# 3Wheel_MotorDrivers_Encoders.net
KiCad netlist of a schematic drawn in Altium Designer
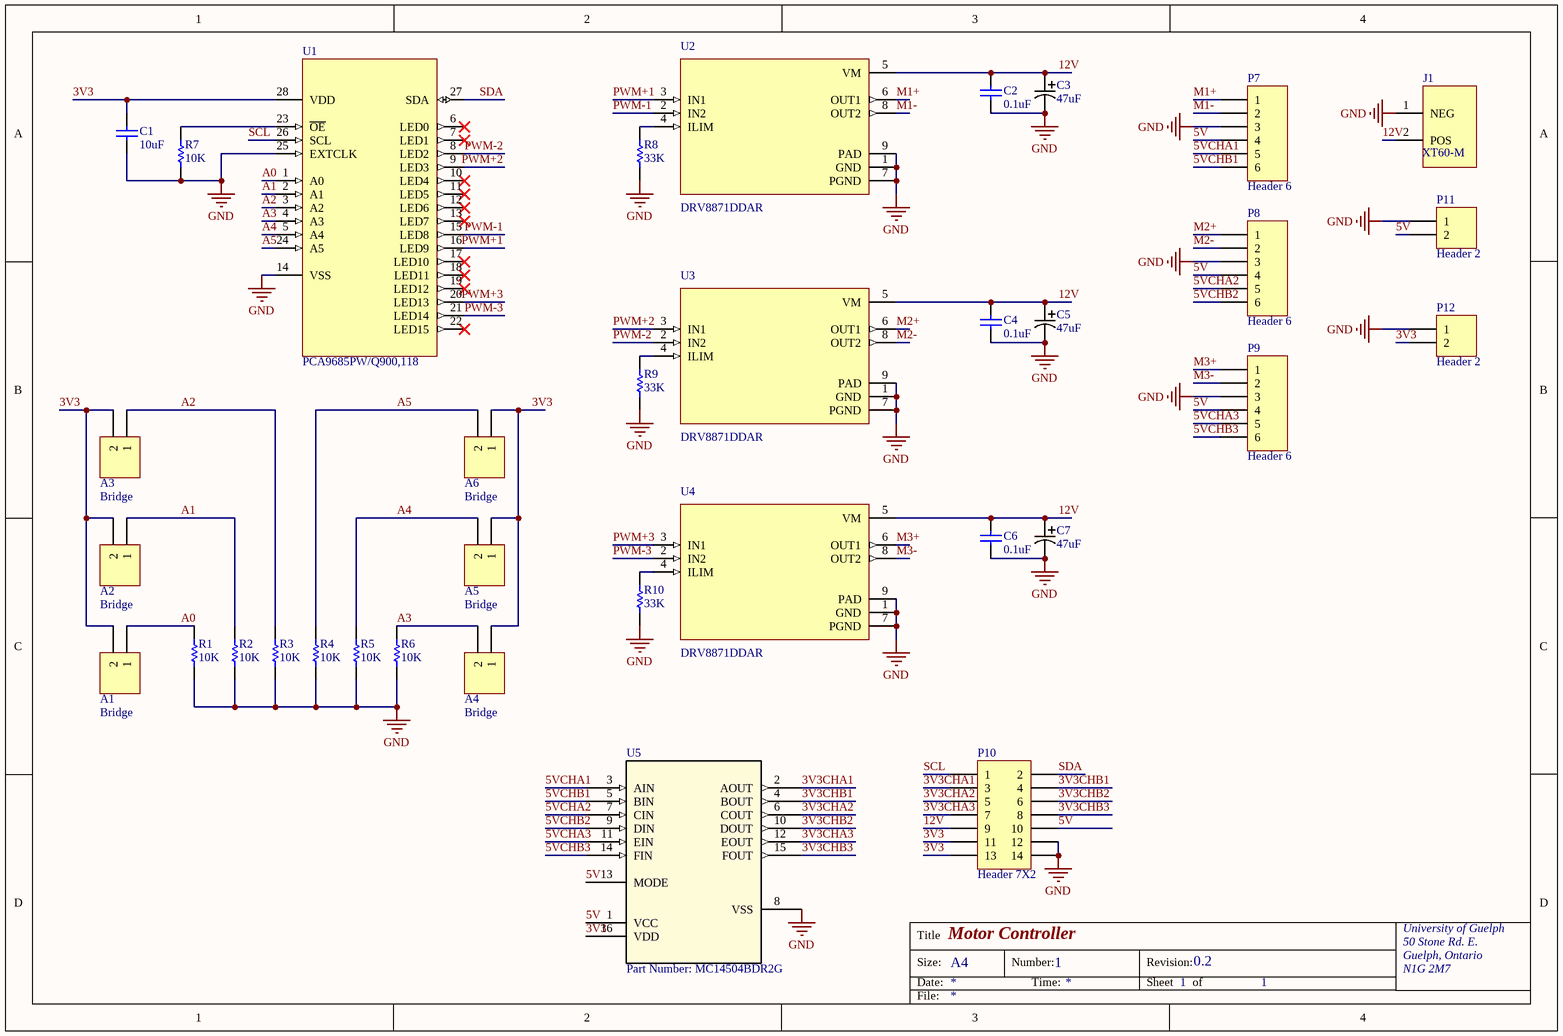
[diagram p0: 3Wheel_MotorDrivers_Encoders.SchDoc]

(export (version "E")
  (design (tool "Eeschema 10.0.6"))
  (components
    (comp (ref "A1")
      (value "Bridge")
      (footprint "0603")
      (description "Header, 2-Pin")
      (fields (field (name "PUBLISHER") "Altium Limited"))
      (libsource (lib "Miscellaneous Connectors") (part "Header 2"))
    )
    (comp (ref "A2")
      (value "Bridge")
      (footprint "0603")
      (description "Header, 2-Pin")
      (fields (field (name "PUBLISHER") "Altium Limited"))
      (libsource (lib "Miscellaneous Connectors") (part "Header 2"))
    )
    (comp (ref "A3")
      (value "Bridge")
      (footprint "0603")
      (description "Header, 2-Pin")
      (fields (field (name "PUBLISHER") "Altium Limited"))
      (libsource (lib "Miscellaneous Connectors") (part "Header 2"))
    )
    (comp (ref "A4")
      (value "Bridge")
      (footprint "0603")
      (description "Header, 2-Pin")
      (fields (field (name "PUBLISHER") "Altium Limited"))
      (libsource (lib "Miscellaneous Connectors") (part "Header 2"))
    )
    (comp (ref "A5")
      (value "Bridge")
      (footprint "0603")
      (description "Header, 2-Pin")
      (fields (field (name "PUBLISHER") "Altium Limited"))
      (libsource (lib "Miscellaneous Connectors") (part "Header 2"))
    )
    (comp (ref "A6")
      (value "Bridge")
      (footprint "0603")
      (description "Header, 2-Pin")
      (fields (field (name "PUBLISHER") "Altium Limited"))
      (libsource (lib "Miscellaneous Connectors") (part "Header 2"))
    )
    (comp (ref "C1")
      (value "10uF")
      (footprint "6-0805_N")
      (description "Capacitor")
      (fields (field (name "Comment") "Cap") (field (name "PUBLISHER") "Altium Limited"))
      (libsource (lib "Miscellaneous Devices") (part "Cap"))
    )
    (comp (ref "C2")
      (value "0.1uF")
      (footprint "6-0805_N")
      (description "Capacitor")
      (fields (field (name "PUBLISHER") "Altium Limited"))
      (libsource (lib "Miscellaneous Devices") (part "Cap"))
    )
    (comp (ref "C3")
      (value "47uF")
      (footprint "PCAP_6.3x7.7-ELE")
      (description "No Description Available")
      (fields
        (field (name "MANUFACTURER_PART_NUMBER") "UWT1H470MCL1GS")
        (field (name "COPYRIGHT") "Copyright (C) 2018 Accelerated Designs. All rights reserved")
      )
      (libsource (lib "2020-02-13_23-38-10") (part "UWT1H470MCL1GS"))
    )
    (comp (ref "C4")
      (value "0.1uF")
      (footprint "6-0805_N")
      (description "Capacitor")
      (fields (field (name "PUBLISHER") "Altium Limited"))
      (libsource (lib "Miscellaneous Devices") (part "Cap"))
    )
    (comp (ref "C5")
      (value "47uF")
      (footprint "PCAP_6.3x7.7-ELE")
      (description "No Description Available")
      (fields
        (field (name "MANUFACTURER_PART_NUMBER") "UWT1H470MCL1GS")
        (field (name "COPYRIGHT") "Copyright (C) 2018 Accelerated Designs. All rights reserved")
      )
      (libsource (lib "2020-02-13_23-38-10") (part "UWT1H470MCL1GS"))
    )
    (comp (ref "C6")
      (value "0.1uF")
      (footprint "6-0805_N")
      (description "Capacitor")
      (fields (field (name "PUBLISHER") "Altium Limited"))
      (libsource (lib "Miscellaneous Devices") (part "Cap"))
    )
    (comp (ref "C7")
      (value "47uF")
      (footprint "PCAP_6.3x7.7-ELE")
      (description "No Description Available")
      (fields
        (field (name "MANUFACTURER_PART_NUMBER") "UWT1H470MCL1GS")
        (field (name "COPYRIGHT") "Copyright (C) 2018 Accelerated Designs. All rights reserved")
      )
      (libsource (lib "2020-02-13_23-38-10") (part "UWT1H470MCL1GS"))
    )
    (comp (ref "J1")
      (value "XT60-M")
      (footprint "*AMASS_XT60-M")
      (description "Plug; DC supply; XT60; male; PIN: 2; for cable; soldered; 30A; 500V")
      (fields (field (name "MF") "AMASS"))
      (libsource (lib "XT60-M") (part "XT60-M"))
    )
    (comp (ref "P7")
      (value "Header 6")
      (footprint "HDR1X6")
      (description "Header, 6-Pin")
      (fields (field (name "PUBLISHER") "Altium Limited"))
      (libsource (lib "Miscellaneous Connectors") (part "Header 6"))
    )
    (comp (ref "P8")
      (value "Header 6")
      (footprint "HDR1X6")
      (description "Header, 6-Pin")
      (fields (field (name "PUBLISHER") "Altium Limited"))
      (libsource (lib "Miscellaneous Connectors") (part "Header 6"))
    )
    (comp (ref "P9")
      (value "Header 6")
      (footprint "HDR1X6")
      (description "Header, 6-Pin")
      (fields (field (name "PUBLISHER") "Altium Limited"))
      (libsource (lib "Miscellaneous Connectors") (part "Header 6"))
    )
    (comp (ref "P10")
      (value "Header 7X2")
      (footprint "HDR2X7")
      (description "Header, 7-Pin, Dual row")
      (fields (field (name "PUBLISHER") "Altium Limited"))
      (libsource (lib "Miscellaneous Connectors") (part "Header 7X2"))
    )
    (comp (ref "P11")
      (value "Header 2")
      (footprint "HDR1X2")
      (description "Header, 2-Pin")
      (fields (field (name "PUBLISHER") "Altium Limited"))
      (libsource (lib "") (part "Header 2_1"))
    )
    (comp (ref "P12")
      (value "Header 2")
      (footprint "HDR1X2")
      (description "Header, 2-Pin")
      (fields (field (name "PUBLISHER") "Altium Limited"))
      (libsource (lib "") (part "Header 2_1"))
    )
    (comp (ref "R1")
      (value "10K")
      (footprint "6-0805_N")
      (description "Resistor")
      (fields (field (name "PUBLISHER") "Altium Limited"))
      (libsource (lib "Miscellaneous Devices") (part "Res1"))
    )
    (comp (ref "R2")
      (value "10K")
      (footprint "6-0805_N")
      (description "Resistor")
      (fields (field (name "PUBLISHER") "Altium Limited"))
      (libsource (lib "Miscellaneous Devices") (part "Res1"))
    )
    (comp (ref "R3")
      (value "10K")
      (footprint "6-0805_N")
      (description "Resistor")
      (fields (field (name "PUBLISHER") "Altium Limited"))
      (libsource (lib "Miscellaneous Devices") (part "Res1"))
    )
    (comp (ref "R4")
      (value "10K")
      (footprint "6-0805_N")
      (description "Resistor")
      (fields (field (name "PUBLISHER") "Altium Limited"))
      (libsource (lib "Miscellaneous Devices") (part "Res1"))
    )
    (comp (ref "R5")
      (value "10K")
      (footprint "6-0805_N")
      (description "Resistor")
      (fields (field (name "PUBLISHER") "Altium Limited"))
      (libsource (lib "Miscellaneous Devices") (part "Res1"))
    )
    (comp (ref "R6")
      (value "10K")
      (footprint "6-0805_N")
      (description "Resistor")
      (fields (field (name "PUBLISHER") "Altium Limited"))
      (libsource (lib "Miscellaneous Devices") (part "Res1"))
    )
    (comp (ref "R7")
      (value "10K")
      (footprint "6-0805_N")
      (description "Resistor")
      (fields (field (name "Comment") "Res1") (field (name "PUBLISHER") "Altium Limited"))
      (libsource (lib "Miscellaneous Devices") (part "Res1"))
    )
    (comp (ref "R8")
      (value "33K")
      (footprint "6-0805_N")
      (description "Resistor")
      (fields (field (name "Comment") "Res1") (field (name "PUBLISHER") "Altium Limited"))
      (libsource (lib "Miscellaneous Devices") (part "Res1"))
    )
    (comp (ref "R9")
      (value "33K")
      (footprint "6-0805_N")
      (description "Resistor")
      (fields (field (name "Comment") "Res1") (field (name "PUBLISHER") "Altium Limited"))
      (libsource (lib "Miscellaneous Devices") (part "Res1"))
    )
    (comp (ref "R10")
      (value "33K")
      (footprint "6-0805_N")
      (description "Resistor")
      (fields (field (name "Comment") "Res1") (field (name "PUBLISHER") "Altium Limited"))
      (libsource (lib "Miscellaneous Devices") (part "Res1"))
    )
    (comp (ref "U1")
      (value "PCA9685PW/Q900,118")
      (footprint "*SOP65P640X110-28N")
      (description "LED Driver IC 16 Output Linear PWM Dimming 25mA 28-TSSOP")
      (fields (field (name "MF") "NXP USA") (field (name "DIGI-KEY_PART_NUMBER") "568-5931-1-ND"))
      (libsource (lib "PCA9685PW_Q900_118") (part "PCA9685PW/Q900,118"))
    )
    (comp (ref "U2")
      (value "DRV8871DDAR")
      (footprint "*SOIC127P600X170-8N")
      (description "Unipolar Motor Driver NMOS PWM 8-SO PowerPad")
      (fields (field (name "DIGI-KEY_PART_NUMBER") "296-43024-1-ND") (field (name "MF") "Texas Instruments"))
      (libsource (lib "DRV8871DDAR") (part "DRV8871DDAR"))
    )
    (comp (ref "U3")
      (value "DRV8871DDAR")
      (footprint "*SOIC127P600X170-8N")
      (description "Unipolar Motor Driver NMOS PWM 8-SO PowerPad")
      (fields (field (name "DIGI-KEY_PART_NUMBER") "296-43024-1-ND") (field (name "MF") "Texas Instruments"))
      (libsource (lib "DRV8871DDAR") (part "DRV8871DDAR"))
    )
    (comp (ref "U4")
      (value "DRV8871DDAR")
      (footprint "*SOIC127P600X170-8N")
      (description "Unipolar Motor Driver NMOS PWM 8-SO PowerPad")
      (fields (field (name "DIGI-KEY_PART_NUMBER") "296-43024-1-ND") (field (name "MF") "Texas Instruments"))
      (libsource (lib "DRV8871DDAR") (part "DRV8871DDAR"))
    )
    (comp (ref "U5")
      (value "Part Number: MC14504BDR2G")
      (footprint "SOIC-16")
      (description "No Description Available")
      (fields
        (field (name "MANUFACTURER_PART_NUMBER") "MC14504BDR2G")
        (field (name "COPYRIGHT") "Copyright (C) 2016 Accelerated Designs. All rights reserved")
      )
      (libsource (lib "2020-02-13_23-03-03") (part "MC14504BDR2G"))
    )
  )
  (nets
    (net (code "1") (name "/3V3") (class "Default")
      (node (ref "A1") (pin "2") (pinfunction "2_2") (pintype "passive"))
      (node (ref "A2") (pin "2") (pinfunction "2_2") (pintype "passive"))
      (node (ref "A3") (pin "2") (pinfunction "2_2") (pintype "passive"))
      (node (ref "A4") (pin "1") (pinfunction "1_1") (pintype "passive"))
      (node (ref "A5") (pin "1") (pinfunction "1_1") (pintype "passive"))
      (node (ref "A6") (pin "1") (pinfunction "1_1") (pintype "passive"))
      (node (ref "C1") (pin "2") (pinfunction "2_2") (pintype "passive"))
      (node (ref "P10") (pin "11") (pinfunction "11_11") (pintype "passive"))
      (node (ref "P10") (pin "13") (pinfunction "13_13") (pintype "passive"))
      (node (ref "P12") (pin "2") (pinfunction "2_2") (pintype "passive"))
      (node (ref "U1") (pin "28") (pinfunction "VDD_28") (pintype "power_in"))
      (node (ref "U5") (pin "16") (pinfunction "VDD_16") (pintype "power_in"))
    )
    (net (code "2") (name "/3V3CHA1") (class "Default")
      (node (ref "P10") (pin "3") (pinfunction "3_3") (pintype "passive"))
      (node (ref "U5") (pin "2") (pinfunction "AOUT_2") (pintype "output"))
    )
    (net (code "3") (name "/3V3CHA2") (class "Default")
      (node (ref "P10") (pin "5") (pinfunction "5_5") (pintype "passive"))
      (node (ref "U5") (pin "6") (pinfunction "COUT_6") (pintype "output"))
    )
    (net (code "4") (name "/3V3CHA3") (class "Default")
      (node (ref "P10") (pin "7") (pinfunction "7_7") (pintype "passive"))
      (node (ref "U5") (pin "12") (pinfunction "EOUT_12") (pintype "output"))
    )
    (net (code "5") (name "/3V3CHB1") (class "Default")
      (node (ref "P10") (pin "4") (pinfunction "4_4") (pintype "passive"))
      (node (ref "U5") (pin "4") (pinfunction "BOUT_4") (pintype "output"))
    )
    (net (code "6") (name "/3V3CHB2") (class "Default")
      (node (ref "P10") (pin "6") (pinfunction "6_6") (pintype "passive"))
      (node (ref "U5") (pin "10") (pinfunction "DOUT_10") (pintype "output"))
    )
    (net (code "7") (name "/3V3CHB3") (class "Default")
      (node (ref "P10") (pin "8") (pinfunction "8_8") (pintype "passive"))
      (node (ref "U5") (pin "15") (pinfunction "FOUT_15") (pintype "output"))
    )
    (net (code "8") (name "/5V") (class "Default")
      (node (ref "P10") (pin "10") (pinfunction "10_10") (pintype "passive"))
      (node (ref "P11") (pin "2") (pinfunction "2_2") (pintype "passive"))
      (node (ref "P7") (pin "4") (pinfunction "4_4") (pintype "passive"))
      (node (ref "P8") (pin "4") (pinfunction "4_4") (pintype "passive"))
      (node (ref "P9") (pin "4") (pinfunction "4_4") (pintype "passive"))
      (node (ref "U5") (pin "1") (pinfunction "VCC_1") (pintype "power_in"))
      (node (ref "U5") (pin "13") (pinfunction "MODE_13") (pintype "passive"))
    )
    (net (code "9") (name "/5VCHA1") (class "Default")
      (node (ref "P7") (pin "5") (pinfunction "5_5") (pintype "passive"))
      (node (ref "U5") (pin "3") (pinfunction "AIN_3") (pintype "input"))
    )
    (net (code "10") (name "/5VCHA2") (class "Default")
      (node (ref "P8") (pin "5") (pinfunction "5_5") (pintype "passive"))
      (node (ref "U5") (pin "7") (pinfunction "CIN_7") (pintype "input"))
    )
    (net (code "11") (name "/5VCHA3") (class "Default")
      (node (ref "P9") (pin "5") (pinfunction "5_5") (pintype "passive"))
      (node (ref "U5") (pin "11") (pinfunction "EIN_11") (pintype "input"))
    )
    (net (code "12") (name "/5VCHB1") (class "Default")
      (node (ref "P7") (pin "6") (pinfunction "6_6") (pintype "passive"))
      (node (ref "U5") (pin "5") (pinfunction "BIN_5") (pintype "input"))
    )
    (net (code "13") (name "/5VCHB2") (class "Default")
      (node (ref "P8") (pin "6") (pinfunction "6_6") (pintype "passive"))
      (node (ref "U5") (pin "9") (pinfunction "DIN_9") (pintype "input"))
    )
    (net (code "14") (name "/5VCHB3") (class "Default")
      (node (ref "P9") (pin "6") (pinfunction "6_6") (pintype "passive"))
      (node (ref "U5") (pin "14") (pinfunction "FIN_14") (pintype "input"))
    )
    (net (code "15") (name "/12V") (class "Default")
      (node (ref "C2") (pin "2") (pinfunction "2_2") (pintype "passive"))
      (node (ref "C3") (pin "1") (pinfunction "1_1") (pintype "passive"))
      (node (ref "C4") (pin "2") (pinfunction "2_2") (pintype "passive"))
      (node (ref "C5") (pin "1") (pinfunction "1_1") (pintype "passive"))
      (node (ref "C6") (pin "2") (pinfunction "2_2") (pintype "passive"))
      (node (ref "C7") (pin "1") (pinfunction "1_1") (pintype "passive"))
      (node (ref "J1") (pin "2") (pinfunction "POS_2") (pintype "passive"))
      (node (ref "P10") (pin "9") (pinfunction "9_9") (pintype "passive"))
      (node (ref "U2") (pin "5") (pinfunction "VM_5") (pintype "power_in"))
      (node (ref "U3") (pin "5") (pinfunction "VM_5") (pintype "power_in"))
      (node (ref "U4") (pin "5") (pinfunction "VM_5") (pintype "power_in"))
    )
    (net (code "16") (name "/A0") (class "Default")
      (node (ref "A1") (pin "1") (pinfunction "1_1") (pintype "passive"))
      (node (ref "R1") (pin "2") (pinfunction "2_2") (pintype "passive"))
      (node (ref "U1") (pin "1") (pinfunction "A0_1") (pintype "input"))
    )
    (net (code "17") (name "/A1") (class "Default")
      (node (ref "A2") (pin "1") (pinfunction "1_1") (pintype "passive"))
      (node (ref "R2") (pin "2") (pinfunction "2_2") (pintype "passive"))
      (node (ref "U1") (pin "2") (pinfunction "A1_2") (pintype "input"))
    )
    (net (code "18") (name "/A2") (class "Default")
      (node (ref "A3") (pin "1") (pinfunction "1_1") (pintype "passive"))
      (node (ref "R3") (pin "2") (pinfunction "2_2") (pintype "passive"))
      (node (ref "U1") (pin "3") (pinfunction "A2_3") (pintype "input"))
    )
    (net (code "19") (name "/A3") (class "Default")
      (node (ref "A4") (pin "2") (pinfunction "2_2") (pintype "passive"))
      (node (ref "R6") (pin "2") (pinfunction "2_2") (pintype "passive"))
      (node (ref "U1") (pin "4") (pinfunction "A3_4") (pintype "input"))
    )
    (net (code "20") (name "/A4") (class "Default")
      (node (ref "A5") (pin "2") (pinfunction "2_2") (pintype "passive"))
      (node (ref "R5") (pin "2") (pinfunction "2_2") (pintype "passive"))
      (node (ref "U1") (pin "5") (pinfunction "A4_5") (pintype "input"))
    )
    (net (code "21") (name "/A5") (class "Default")
      (node (ref "A6") (pin "2") (pinfunction "2_2") (pintype "passive"))
      (node (ref "R4") (pin "2") (pinfunction "2_2") (pintype "passive"))
      (node (ref "U1") (pin "24") (pinfunction "A5_24") (pintype "input"))
    )
    (net (code "22") (name "/M1+") (class "Default")
      (node (ref "P7") (pin "1") (pinfunction "1_1") (pintype "passive"))
      (node (ref "U2") (pin "6") (pinfunction "OUT1_6") (pintype "output"))
    )
    (net (code "23") (name "/M1-") (class "Default")
      (node (ref "P7") (pin "2") (pinfunction "2_2") (pintype "passive"))
      (node (ref "U2") (pin "8") (pinfunction "OUT2_8") (pintype "output"))
    )
    (net (code "24") (name "/M2+") (class "Default")
      (node (ref "P8") (pin "1") (pinfunction "1_1") (pintype "passive"))
      (node (ref "U3") (pin "6") (pinfunction "OUT1_6") (pintype "output"))
    )
    (net (code "25") (name "/M2-") (class "Default")
      (node (ref "P8") (pin "2") (pinfunction "2_2") (pintype "passive"))
      (node (ref "U3") (pin "8") (pinfunction "OUT2_8") (pintype "output"))
    )
    (net (code "26") (name "/M3+") (class "Default")
      (node (ref "P9") (pin "1") (pinfunction "1_1") (pintype "passive"))
      (node (ref "U4") (pin "6") (pinfunction "OUT1_6") (pintype "output"))
    )
    (net (code "27") (name "/M3-") (class "Default")
      (node (ref "P9") (pin "2") (pinfunction "2_2") (pintype "passive"))
      (node (ref "U4") (pin "8") (pinfunction "OUT2_8") (pintype "output"))
    )
    (net (code "28") (name "/PWM+1") (class "Default")
      (node (ref "U1") (pin "16") (pinfunction "LED9_16") (pintype "output"))
      (node (ref "U2") (pin "3") (pinfunction "IN1_3") (pintype "input"))
    )
    (net (code "29") (name "/PWM+2") (class "Default")
      (node (ref "U1") (pin "9") (pinfunction "LED3_9") (pintype "output"))
      (node (ref "U3") (pin "3") (pinfunction "IN1_3") (pintype "input"))
    )
    (net (code "30") (name "/PWM+3") (class "Default")
      (node (ref "U1") (pin "20") (pinfunction "LED13_20") (pintype "output"))
      (node (ref "U4") (pin "3") (pinfunction "IN1_3") (pintype "input"))
    )
    (net (code "31") (name "/PWM-1") (class "Default")
      (node (ref "U1") (pin "15") (pinfunction "LED8_15") (pintype "output"))
      (node (ref "U2") (pin "2") (pinfunction "IN2_2") (pintype "input"))
    )
    (net (code "32") (name "/PWM-2") (class "Default")
      (node (ref "U1") (pin "8") (pinfunction "LED2_8") (pintype "output"))
      (node (ref "U3") (pin "2") (pinfunction "IN2_2") (pintype "input"))
    )
    (net (code "33") (name "/PWM-3") (class "Default")
      (node (ref "U1") (pin "21") (pinfunction "LED14_21") (pintype "output"))
      (node (ref "U4") (pin "2") (pinfunction "IN2_2") (pintype "input"))
    )
    (net (code "34") (name "/SCL") (class "Default")
      (node (ref "P10") (pin "1") (pinfunction "1_1") (pintype "passive"))
      (node (ref "U1") (pin "26") (pinfunction "SCL_26") (pintype "input"))
    )
    (net (code "35") (name "/SDA") (class "Default")
      (node (ref "P10") (pin "2") (pinfunction "2_2") (pintype "passive"))
      (node (ref "U1") (pin "27") (pinfunction "SDA_27") (pintype "bidirectional"))
    )
    (net (code "36") (name "GND") (class "Default")
      (node (ref "C1") (pin "1") (pinfunction "1_1") (pintype "passive"))
      (node (ref "C2") (pin "1") (pinfunction "1_1") (pintype "passive"))
      (node (ref "C3") (pin "2") (pinfunction "2_2") (pintype "passive"))
      (node (ref "C4") (pin "1") (pinfunction "1_1") (pintype "passive"))
      (node (ref "C5") (pin "2") (pinfunction "2_2") (pintype "passive"))
      (node (ref "C6") (pin "1") (pinfunction "1_1") (pintype "passive"))
      (node (ref "C7") (pin "2") (pinfunction "2_2") (pintype "passive"))
      (node (ref "J1") (pin "1") (pinfunction "NEG_1") (pintype "passive"))
      (node (ref "P10") (pin "12") (pinfunction "12_12") (pintype "passive"))
      (node (ref "P10") (pin "14") (pinfunction "14_14") (pintype "passive"))
      (node (ref "P11") (pin "1") (pinfunction "1_1") (pintype "passive"))
      (node (ref "P12") (pin "1") (pinfunction "1_1") (pintype "passive"))
      (node (ref "P7") (pin "3") (pinfunction "3_3") (pintype "passive"))
      (node (ref "P8") (pin "3") (pinfunction "3_3") (pintype "passive"))
      (node (ref "P9") (pin "3") (pinfunction "3_3") (pintype "passive"))
      (node (ref "R1") (pin "1") (pinfunction "1_1") (pintype "passive"))
      (node (ref "R10") (pin "1") (pinfunction "1_1") (pintype "passive"))
      (node (ref "R2") (pin "1") (pinfunction "1_1") (pintype "passive"))
      (node (ref "R3") (pin "1") (pinfunction "1_1") (pintype "passive"))
      (node (ref "R4") (pin "1") (pinfunction "1_1") (pintype "passive"))
      (node (ref "R5") (pin "1") (pinfunction "1_1") (pintype "passive"))
      (node (ref "R6") (pin "1") (pinfunction "1_1") (pintype "passive"))
      (node (ref "R7") (pin "1") (pinfunction "1_1") (pintype "passive"))
      (node (ref "R8") (pin "1") (pinfunction "1_1") (pintype "passive"))
      (node (ref "R9") (pin "1") (pinfunction "1_1") (pintype "passive"))
      (node (ref "U1") (pin "14") (pinfunction "VSS_14") (pintype "passive"))
      (node (ref "U1") (pin "25") (pinfunction "EXTCLK_25") (pintype "input"))
      (node (ref "U2") (pin "1") (pinfunction "GND_1") (pintype "power_in"))
      (node (ref "U2") (pin "7") (pinfunction "PGND_7") (pintype "power_in"))
      (node (ref "U2") (pin "9") (pinfunction "PAD_9") (pintype "power_in"))
      (node (ref "U3") (pin "1") (pinfunction "GND_1") (pintype "power_in"))
      (node (ref "U3") (pin "7") (pinfunction "PGND_7") (pintype "power_in"))
      (node (ref "U3") (pin "9") (pinfunction "PAD_9") (pintype "power_in"))
      (node (ref "U4") (pin "1") (pinfunction "GND_1") (pintype "power_in"))
      (node (ref "U4") (pin "7") (pinfunction "PGND_7") (pintype "power_in"))
      (node (ref "U4") (pin "9") (pinfunction "PAD_9") (pintype "power_in"))
      (node (ref "U5") (pin "8") (pinfunction "VSS_8") (pintype "power_in"))
    )
    (net (code "37") (name "Net-(U1-~{OE})") (class "Default")
      (node (ref "R7") (pin "2") (pinfunction "2_2") (pintype "passive"))
      (node (ref "U1") (pin "23") (pinfunction "~{OE}_23") (pintype "input"))
    )
    (net (code "38") (name "Net-(U2-ILIM)") (class "Default")
      (node (ref "R8") (pin "2") (pinfunction "2_2") (pintype "passive"))
      (node (ref "U2") (pin "4") (pinfunction "ILIM_4") (pintype "input"))
    )
    (net (code "39") (name "Net-(U3-ILIM)") (class "Default")
      (node (ref "R9") (pin "2") (pinfunction "2_2") (pintype "passive"))
      (node (ref "U3") (pin "4") (pinfunction "ILIM_4") (pintype "input"))
    )
    (net (code "40") (name "Net-(U4-ILIM)") (class "Default")
      (node (ref "R10") (pin "2") (pinfunction "2_2") (pintype "passive"))
      (node (ref "U4") (pin "4") (pinfunction "ILIM_4") (pintype "input"))
    )
    (net (code "41") (name "unconnected-(U1-LED0-Pad6)") (class "Default")
      (node (ref "U1") (pin "6") (pinfunction "LED0_6") (pintype "output+no_connect"))
    )
    (net (code "42") (name "unconnected-(U1-LED1-Pad7)") (class "Default")
      (node (ref "U1") (pin "7") (pinfunction "LED1_7") (pintype "output+no_connect"))
    )
    (net (code "43") (name "unconnected-(U1-LED4-Pad10)") (class "Default")
      (node (ref "U1") (pin "10") (pinfunction "LED4_10") (pintype "output+no_connect"))
    )
    (net (code "44") (name "unconnected-(U1-LED5-Pad11)") (class "Default")
      (node (ref "U1") (pin "11") (pinfunction "LED5_11") (pintype "output+no_connect"))
    )
    (net (code "45") (name "unconnected-(U1-LED6-Pad12)") (class "Default")
      (node (ref "U1") (pin "12") (pinfunction "LED6_12") (pintype "output+no_connect"))
    )
    (net (code "46") (name "unconnected-(U1-LED7-Pad13)") (class "Default")
      (node (ref "U1") (pin "13") (pinfunction "LED7_13") (pintype "output+no_connect"))
    )
    (net (code "47") (name "unconnected-(U1-LED10-Pad17)") (class "Default")
      (node (ref "U1") (pin "17") (pinfunction "LED10_17") (pintype "output+no_connect"))
    )
    (net (code "48") (name "unconnected-(U1-LED11-Pad18)") (class "Default")
      (node (ref "U1") (pin "18") (pinfunction "LED11_18") (pintype "output+no_connect"))
    )
    (net (code "49") (name "unconnected-(U1-LED12-Pad19)") (class "Default")
      (node (ref "U1") (pin "19") (pinfunction "LED12_19") (pintype "output+no_connect"))
    )
    (net (code "50") (name "unconnected-(U1-LED15-Pad22)") (class "Default")
      (node (ref "U1") (pin "22") (pinfunction "LED15_22") (pintype "output+no_connect"))
    )
  )
)
